# Placa.net
KiCad netlist of a schematic drawn in EAGLE
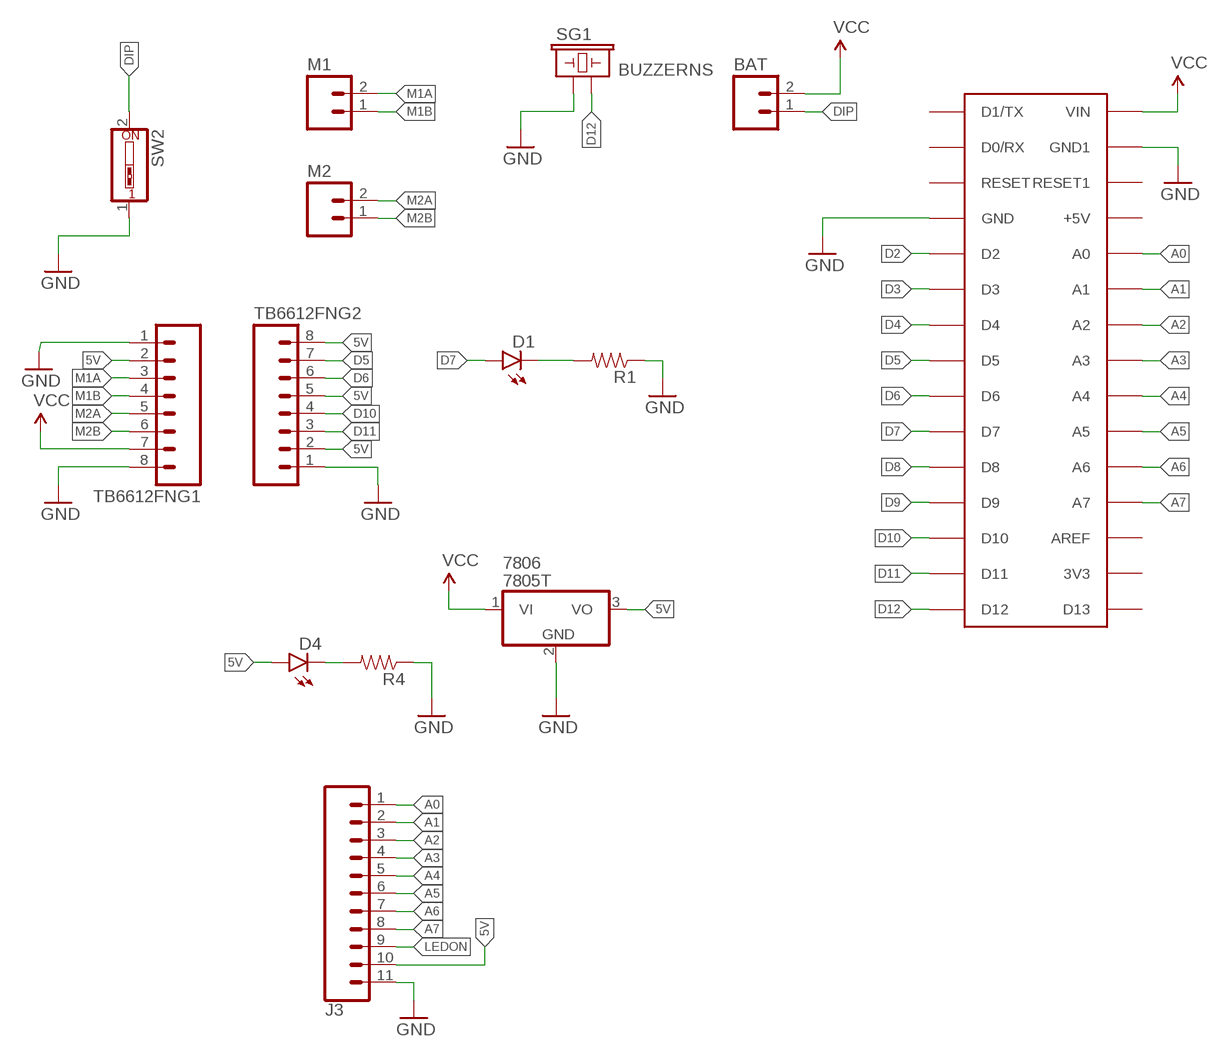
[diagram p0: schematic, sheet 1]

(export (version "E")
  (design (tool "Eeschema 10.0.6"))
  (components
    (comp (ref "7806")
      (value "7805T")
      (footprint "eagle-import:TO220H")
      (libsource (lib "eagle-import") (part "78T05"))
    )
    (comp (ref "BAT")
      (value "M02PTH")
      (footprint "eagle-import:1X02@1")
      (libsource (lib "eagle-import") (part "M02PTH"))
    )
    (comp (ref "D1")
      (value "LED5MM")
      (footprint "eagle-import:LED5MM")
      (libsource (lib "eagle-import") (part "LED5MM"))
    )
    (comp (ref "D4")
      (value "LED5MM")
      (footprint "eagle-import:LED5MM")
      (libsource (lib "eagle-import") (part "LED5MM"))
    )
    (comp (ref "J3")
      (value "CONN_11")
      (footprint "eagle-import:1X11")
      (libsource (lib "eagle-import") (part "CONN_11"))
    )
    (comp (ref "M1")
      (value "M02JST-PTH-VERT")
      (footprint "eagle-import:JST-2-PTH-VERT")
      (libsource (lib "eagle-import") (part "M02JST-PTH-VERT"))
    )
    (comp (ref "M2")
      (value "M02JST-PTH-VERT")
      (footprint "eagle-import:JST-2-PTH-VERT")
      (libsource (lib "eagle-import") (part "M02JST-PTH-VERT"))
    )
    (comp (ref "R1")
      (value "RESISTOREZ")
      (footprint "eagle-import:AXIAL-0.3EZ")
      (libsource (lib "eagle-import") (part "RESISTOREZ"))
    )
    (comp (ref "R4")
      (value "RESISTOREZ")
      (footprint "eagle-import:AXIAL-0.3EZ")
      (libsource (lib "eagle-import") (part "RESISTOREZ"))
    )
    (comp (ref "SG1")
      (value "BUZZERNS")
      (footprint "eagle-import:BUZZER-12MM-NS")
      (libsource (lib "eagle-import") (part "BUZZERNS"))
    )
    (comp (ref "SW2")
      (value "SW_DIP-1")
      (footprint "eagle-import:EDG-01")
      (libsource (lib "eagle-import") (part "SW_DIP-1"))
    )
    (comp (ref "TB6612FNG1")
      (value "M08")
      (footprint "eagle-import:1X08_ROUND")
      (libsource (lib "eagle-import") (part "M08"))
    )
    (comp (ref "TB6612FNG2")
      (value "M08")
      (footprint "eagle-import:1X08_ROUND")
      (libsource (lib "eagle-import") (part "M08"))
    )
    (comp (ref "U1")
      (value "NANO")
      (footprint "eagle-import:PDIP-32")
      (libsource (lib "eagle-import") (part "ARDUINONANO"))
    )
  )
  (nets
    (net (code "1") (name "5V") (class "Default")
      (node (ref "7806") (pin "3") (pinfunction "VO_3") (pintype "passive"))
      (node (ref "D4") (pin "A") (pinfunction "A_A") (pintype "passive"))
      (node (ref "J3") (pin "10") (pinfunction "10_10") (pintype "passive"))
      (node (ref "TB6612FNG1") (pin "2") (pinfunction "2_2") (pintype "passive"))
      (node (ref "TB6612FNG2") (pin "2") (pinfunction "2_2") (pintype "passive"))
      (node (ref "TB6612FNG2") (pin "5") (pinfunction "5_5") (pintype "passive"))
      (node (ref "TB6612FNG2") (pin "8") (pinfunction "8_8") (pintype "passive"))
    )
    (net (code "2") (name "A0") (class "Default")
      (node (ref "J3") (pin "1") (pinfunction "1_1") (pintype "passive"))
      (node (ref "U1") (pin "A0") (pinfunction "A0_A0") (pintype "bidirectional"))
    )
    (net (code "3") (name "A1") (class "Default")
      (node (ref "J3") (pin "2") (pinfunction "2_2") (pintype "passive"))
      (node (ref "U1") (pin "A1") (pinfunction "A1_A1") (pintype "bidirectional"))
    )
    (net (code "4") (name "A2") (class "Default")
      (node (ref "J3") (pin "3") (pinfunction "3_3") (pintype "passive"))
      (node (ref "U1") (pin "A2") (pinfunction "A2_A2") (pintype "bidirectional"))
    )
    (net (code "5") (name "A3") (class "Default")
      (node (ref "J3") (pin "4") (pinfunction "4_4") (pintype "passive"))
      (node (ref "U1") (pin "A3") (pinfunction "A3_A3") (pintype "bidirectional"))
    )
    (net (code "6") (name "A4") (class "Default")
      (node (ref "J3") (pin "5") (pinfunction "5_5") (pintype "passive"))
      (node (ref "U1") (pin "A4") (pinfunction "A4_A4") (pintype "bidirectional"))
    )
    (net (code "7") (name "A5") (class "Default")
      (node (ref "J3") (pin "6") (pinfunction "6_6") (pintype "passive"))
      (node (ref "U1") (pin "A5") (pinfunction "A5_A5") (pintype "bidirectional"))
    )
    (net (code "8") (name "A6") (class "Default")
      (node (ref "J3") (pin "7") (pinfunction "7_7") (pintype "passive"))
      (node (ref "U1") (pin "A6") (pinfunction "A6_A6") (pintype "bidirectional"))
    )
    (net (code "9") (name "A7") (class "Default")
      (node (ref "J3") (pin "8") (pinfunction "8_8") (pintype "passive"))
      (node (ref "U1") (pin "A7") (pinfunction "A7_A7") (pintype "bidirectional"))
    )
    (net (code "10") (name "D2") (class "Default")
      (node (ref "U1") (pin "D2") (pinfunction "D2_D2") (pintype "bidirectional"))
    )
    (net (code "11") (name "D3") (class "Default")
      (node (ref "U1") (pin "D3") (pinfunction "D3_D3") (pintype "bidirectional"))
    )
    (net (code "12") (name "D4") (class "Default")
      (node (ref "U1") (pin "D4") (pinfunction "D4_D4") (pintype "bidirectional"))
    )
    (net (code "13") (name "D5") (class "Default")
      (node (ref "TB6612FNG2") (pin "7") (pinfunction "7_7") (pintype "passive"))
      (node (ref "U1") (pin "D5") (pinfunction "D5_D5") (pintype "bidirectional"))
    )
    (net (code "14") (name "D6") (class "Default")
      (node (ref "TB6612FNG2") (pin "6") (pinfunction "6_6") (pintype "passive"))
      (node (ref "U1") (pin "D6") (pinfunction "D6_D6") (pintype "bidirectional"))
    )
    (net (code "15") (name "D7") (class "Default")
      (node (ref "D1") (pin "A") (pinfunction "A_A") (pintype "passive"))
      (node (ref "U1") (pin "D7") (pinfunction "D7_D7") (pintype "bidirectional"))
    )
    (net (code "16") (name "D8") (class "Default")
      (node (ref "U1") (pin "D8") (pinfunction "D8_D8") (pintype "bidirectional"))
    )
    (net (code "17") (name "D9") (class "Default")
      (node (ref "U1") (pin "D9") (pinfunction "D9_D9") (pintype "bidirectional"))
    )
    (net (code "18") (name "D10") (class "Default")
      (node (ref "TB6612FNG2") (pin "4") (pinfunction "4_4") (pintype "passive"))
      (node (ref "U1") (pin "D10") (pinfunction "D10_D10") (pintype "bidirectional"))
    )
    (net (code "19") (name "D11") (class "Default")
      (node (ref "TB6612FNG2") (pin "3") (pinfunction "3_3") (pintype "passive"))
      (node (ref "U1") (pin "D11") (pinfunction "D11_D11") (pintype "bidirectional"))
    )
    (net (code "20") (name "D12") (class "Default")
      (node (ref "SG1") (pin "-") (pinfunction "2_-") (pintype "passive"))
      (node (ref "U1") (pin "D12") (pinfunction "D12_D12") (pintype "bidirectional"))
    )
    (net (code "21") (name "DIP") (class "Default")
      (node (ref "BAT") (pin "1") (pinfunction "1_1") (pintype "passive"))
      (node (ref "SW2") (pin "2") (pinfunction "2_2") (pintype "passive"))
    )
    (net (code "22") (name "GND") (class "Default")
      (node (ref "7806") (pin "2") (pinfunction "GND_2") (pintype "passive"))
      (node (ref "J3") (pin "11") (pinfunction "11_11") (pintype "passive"))
      (node (ref "R1") (pin "P$1") (pinfunction "1_P$1") (pintype "passive"))
      (node (ref "R4") (pin "P$1") (pinfunction "1_P$1") (pintype "passive"))
      (node (ref "SG1") (pin "+") (pinfunction "1_+") (pintype "passive"))
      (node (ref "SW2") (pin "1") (pinfunction "1_1") (pintype "passive"))
      (node (ref "TB6612FNG1") (pin "1") (pinfunction "1_1") (pintype "passive"))
      (node (ref "TB6612FNG1") (pin "8") (pinfunction "8_8") (pintype "passive"))
      (node (ref "TB6612FNG2") (pin "1") (pinfunction "1_1") (pintype "passive"))
      (node (ref "U1") (pin "GND") (pinfunction "GND_GND") (pintype "bidirectional"))
      (node (ref "U1") (pin "GND1") (pinfunction "GND1_GND1") (pintype "bidirectional"))
    )
    (net (code "23") (name "LEDON") (class "Default")
      (node (ref "J3") (pin "9") (pinfunction "9_9") (pintype "passive"))
    )
    (net (code "24") (name "M1A") (class "Default")
      (node (ref "M1") (pin "2") (pinfunction "2_2") (pintype "passive"))
      (node (ref "TB6612FNG1") (pin "3") (pinfunction "3_3") (pintype "passive"))
    )
    (net (code "25") (name "M1B") (class "Default")
      (node (ref "M1") (pin "1") (pinfunction "1_1") (pintype "passive"))
      (node (ref "TB6612FNG1") (pin "4") (pinfunction "4_4") (pintype "passive"))
    )
    (net (code "26") (name "M2A") (class "Default")
      (node (ref "M2") (pin "2") (pinfunction "2_2") (pintype "passive"))
      (node (ref "TB6612FNG1") (pin "5") (pinfunction "5_5") (pintype "passive"))
    )
    (net (code "27") (name "M2B") (class "Default")
      (node (ref "M2") (pin "1") (pinfunction "1_1") (pintype "passive"))
      (node (ref "TB6612FNG1") (pin "6") (pinfunction "6_6") (pintype "passive"))
    )
    (net (code "28") (name "Net-(D1-C)") (class "Default")
      (node (ref "D1") (pin "K") (pinfunction "C_K") (pintype "passive"))
      (node (ref "R1") (pin "P$2") (pinfunction "2_P$2") (pintype "passive"))
    )
    (net (code "29") (name "Net-(D4-C)") (class "Default")
      (node (ref "D4") (pin "K") (pinfunction "C_K") (pintype "passive"))
      (node (ref "R4") (pin "P$2") (pinfunction "2_P$2") (pintype "passive"))
    )
    (net (code "30") (name "VCC") (class "Default")
      (node (ref "7806") (pin "1") (pinfunction "VI_1") (pintype "input"))
      (node (ref "BAT") (pin "2") (pinfunction "2_2") (pintype "passive"))
      (node (ref "TB6612FNG1") (pin "7") (pinfunction "7_7") (pintype "passive"))
      (node (ref "U1") (pin "VIN") (pinfunction "VIN_VIN") (pintype "bidirectional"))
    )
    (net (code "31") (name "unconnected-(U1-Pad+5V)") (class "Default")
      (node (ref "U1") (pin "+5V") (pinfunction "+5V_+5V") (pintype "bidirectional"))
    )
    (net (code "32") (name "unconnected-(U1-Pad3V3)") (class "Default")
      (node (ref "U1") (pin "3V3") (pinfunction "3V3_3V3") (pintype "bidirectional"))
    )
    (net (code "33") (name "unconnected-(U1-PadAREF)") (class "Default")
      (node (ref "U1") (pin "AREF") (pinfunction "AREF_AREF") (pintype "bidirectional"))
    )
    (net (code "34") (name "unconnected-(U1-PadD0{slash}RX)") (class "Default")
      (node (ref "U1") (pin "D0/RX") (pinfunction "D0/RX_D0/RX") (pintype "bidirectional"))
    )
    (net (code "35") (name "unconnected-(U1-PadD1{slash}TX)") (class "Default")
      (node (ref "U1") (pin "D1/TX") (pinfunction "D1/TX_D1/TX") (pintype "bidirectional"))
    )
    (net (code "36") (name "unconnected-(U1-PadD13)") (class "Default")
      (node (ref "U1") (pin "D13") (pinfunction "D13_D13") (pintype "bidirectional"))
    )
    (net (code "37") (name "unconnected-(U1-PadRESET)") (class "Default")
      (node (ref "U1") (pin "RESET") (pinfunction "RESET_RESET") (pintype "bidirectional"))
    )
    (net (code "38") (name "unconnected-(U1-PadRESET1)") (class "Default")
      (node (ref "U1") (pin "RESET1") (pinfunction "RESET1_RESET1") (pintype "bidirectional"))
    )
  )
)
